# Sonar.net
KiCad netlist of a schematic drawn in Altium Designer
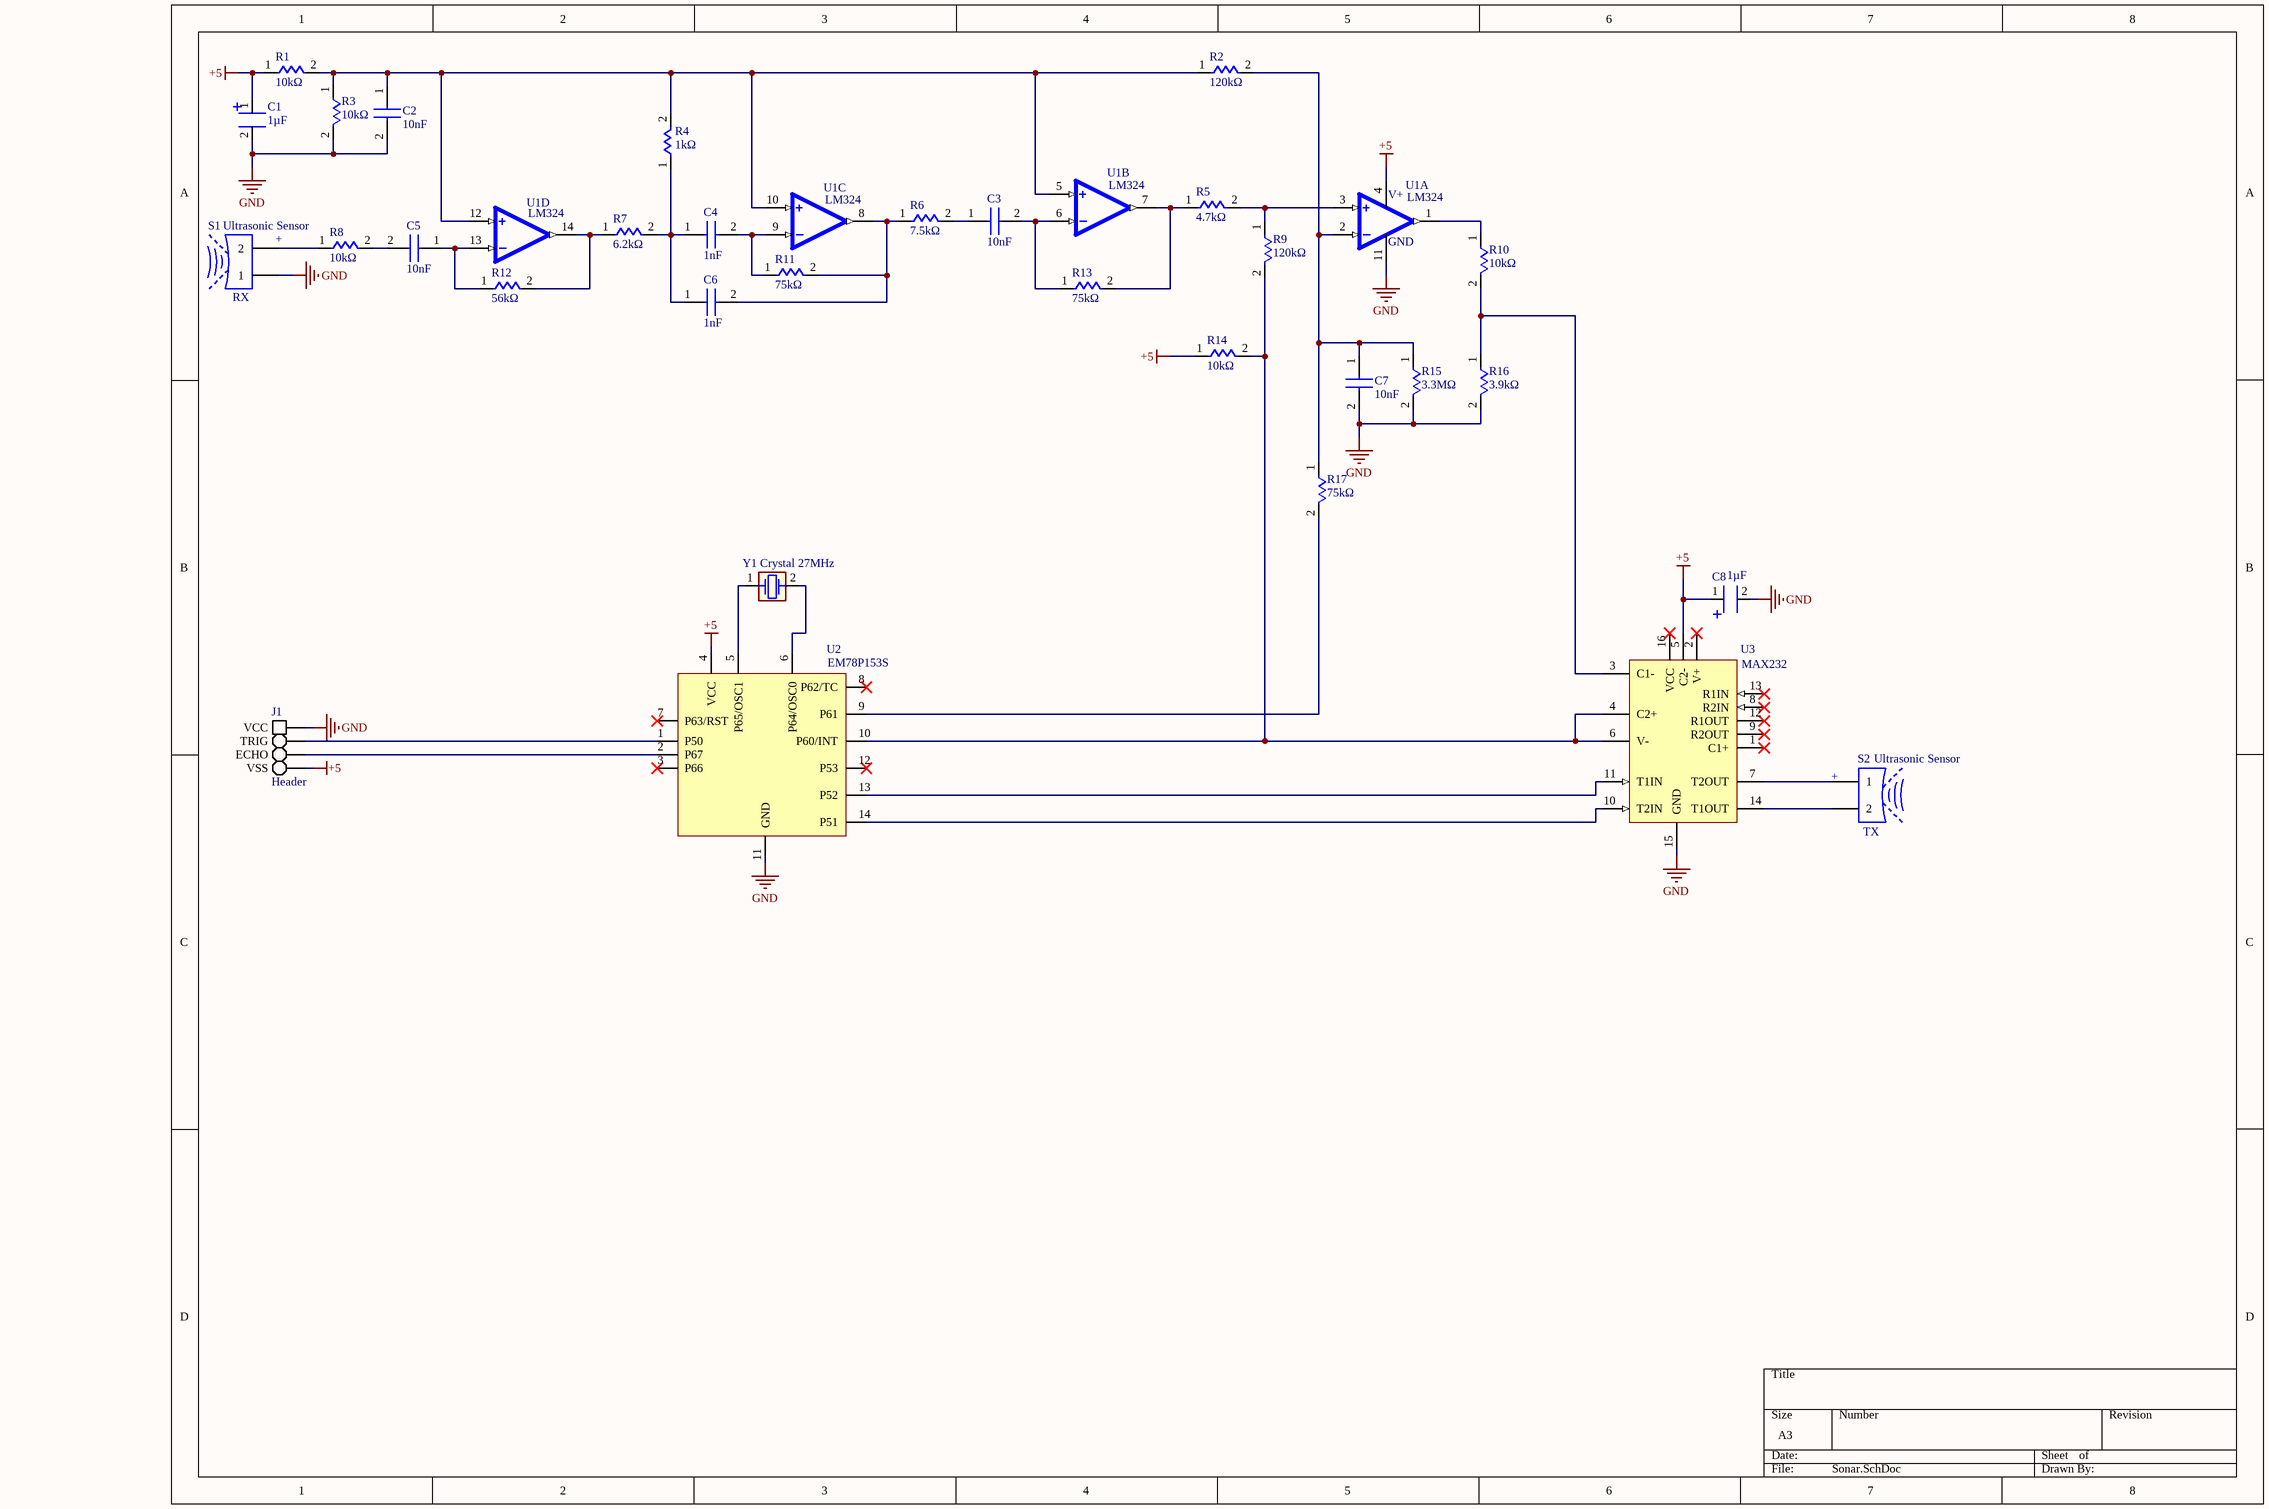
[diagram p0: Sonar.SchDoc]

(export (version "E")
  (design (tool "Eeschema 10.0.6"))
  (components
    (comp (ref "C1")
      (value "1µF")
      (footprint "CAP.EL.")
      (description "MZ1V687M12020PH - CAP.EL.680uF 35V 12.5x20 5MM 105C TB SAMWHA")
      (libsource (lib "Sonar") (part "Cap Pol"))
    )
    (comp (ref "C2")
      (value "10nF")
      (footprint "CAP")
      (description "Capacitor")
      (libsource (lib "Sonar") (part "CAP"))
    )
    (comp (ref "C3")
      (value "10nF")
      (footprint "CAP")
      (description "Capacitor")
      (libsource (lib "Sonar") (part "CAP"))
    )
    (comp (ref "C4")
      (value "1nF")
      (footprint "CAP")
      (description "Capacitor")
      (libsource (lib "Sonar") (part "CAP"))
    )
    (comp (ref "C5")
      (value "10nF")
      (footprint "CAP")
      (description "Capacitor")
      (libsource (lib "Sonar") (part "CAP"))
    )
    (comp (ref "C6")
      (value "1nF")
      (footprint "CAP")
      (description "Capacitor")
      (libsource (lib "Sonar") (part "CAP"))
    )
    (comp (ref "C7")
      (value "10nF")
      (footprint "CAP")
      (description "Capacitor")
      (libsource (lib "Sonar") (part "CAP"))
    )
    (comp (ref "C8")
      (value "1µF")
      (footprint "CAP.EL.")
      (description "MZ1V687M12020PH - CAP.EL.680uF 35V 12.5x20 5MM 105C TB SAMWHA")
      (libsource (lib "Sonar") (part "Cap Pol"))
    )
    (comp (ref "J1") (value "Header") (footprint "Header 1x4") (libsource (lib "Sonar") (part "Header")))
    (comp (ref "R1")
      (value "10kΩ")
      (footprint "THT Res")
      (description "THT RES")
      (libsource (lib "Sonar") (part "THT RES"))
    )
    (comp (ref "R2")
      (value "120kΩ")
      (footprint "THT Res")
      (description "THT RES")
      (libsource (lib "Sonar") (part "THT RES"))
    )
    (comp (ref "R3")
      (value "10kΩ")
      (footprint "THT Res")
      (description "THT RES")
      (libsource (lib "Sonar") (part "THT RES"))
    )
    (comp (ref "R4")
      (value "1kΩ")
      (footprint "THT Res")
      (description "THT RES")
      (libsource (lib "Sonar") (part "THT RES"))
    )
    (comp (ref "R5")
      (value "4.7kΩ")
      (footprint "THT Res")
      (description "THT RES")
      (libsource (lib "Sonar") (part "THT RES"))
    )
    (comp (ref "R6")
      (value "7.5kΩ")
      (footprint "THT Res")
      (description "THT RES")
      (libsource (lib "Sonar") (part "THT RES"))
    )
    (comp (ref "R7")
      (value "6.2kΩ")
      (footprint "THT Res")
      (description "THT RES")
      (libsource (lib "Sonar") (part "THT RES"))
    )
    (comp (ref "R8")
      (value "10kΩ")
      (footprint "THT Res")
      (description "THT RES")
      (libsource (lib "Sonar") (part "THT RES"))
    )
    (comp (ref "R9")
      (value "120kΩ")
      (footprint "THT Res")
      (description "THT RES")
      (libsource (lib "Sonar") (part "THT RES"))
    )
    (comp (ref "R10")
      (value "10kΩ")
      (footprint "THT Res")
      (description "THT RES")
      (libsource (lib "Sonar") (part "THT RES"))
    )
    (comp (ref "R11")
      (value "75kΩ")
      (footprint "THT Res")
      (description "THT RES")
      (libsource (lib "Sonar") (part "THT RES"))
    )
    (comp (ref "R12")
      (value "56kΩ")
      (footprint "THT Res")
      (description "THT RES")
      (libsource (lib "Sonar") (part "THT RES"))
    )
    (comp (ref "R13")
      (value "75kΩ")
      (footprint "THT Res")
      (description "THT RES")
      (libsource (lib "Sonar") (part "THT RES"))
    )
    (comp (ref "R14")
      (value "10kΩ")
      (footprint "THT Res")
      (description "THT RES")
      (libsource (lib "Sonar") (part "THT RES"))
    )
    (comp (ref "R15")
      (value "3.3MΩ")
      (footprint "THT Res")
      (description "THT RES")
      (libsource (lib "Sonar") (part "THT RES"))
    )
    (comp (ref "R16")
      (value "3.9kΩ")
      (footprint "THT Res")
      (description "THT RES")
      (libsource (lib "Sonar") (part "THT RES"))
    )
    (comp (ref "R17")
      (value "75kΩ")
      (footprint "THT Res")
      (description "THT RES")
      (libsource (lib "Sonar") (part "THT RES"))
    )
    (comp (ref "S1")
      (value "Ultrasonic Sensor")
      (footprint "Ultrasonic Sensor")
      (libsource (lib "Sonar") (part "Ultrasonic Sensor"))
    )
    (comp (ref "S2")
      (value "Ultrasonic Sensor")
      (footprint "Ultrasonic Sensor")
      (libsource (lib "Sonar") (part "Ultrasonic Sensor"))
    )
    (comp (ref "U1")
      (value "LM324")
      (footprint "LM324")
      (description "4-Channel industry standard operational amplifier 14-PDIP 0 to 70")
      (fields (field (name "MP") "LM324N") (field (name "MF") "Texas Instruments"))
      (libsource (lib "Sonar") (part "LM324N/NOPB"))
    )
    (comp (ref "U2") (value "EM78P153S") (footprint "EM78P153S") (libsource (lib "Sonar") (part "EM78P153S")))
    (comp (ref "U3")
      (value "MAX232")
      (footprint "MAX232")
      (description "Multichannel RS-232 Driver/Receiver, 5 V, 0 to 70 degC, 16-Pin SOIC (S16+3), RoHS, Tube")
      (fields (field (name "MANUFACTURER") "Maxim"))
      (libsource (lib "Sonar") (part "MAX232"))
    )
    (comp (ref "Y1")
      (value "Crystal 27MHz")
      (footprint "Crsytal")
      (description "27.000 MHz Kristal HC-49S")
      (libsource (lib "Sonar") (part "Crystal"))
    )
  )
  (nets
    (net (code "1") (name "+5") (class "Default")
      (node (ref "C1") (pin "1") (pinfunction "1_1") (pintype "passive"))
      (node (ref "C8") (pin "1") (pinfunction "1_1") (pintype "passive"))
      (node (ref "J1") (pin "4") (pinfunction "VSS_4") (pintype "passive"))
      (node (ref "R1") (pin "1") (pinfunction "1_1") (pintype "passive"))
      (node (ref "R14") (pin "1") (pinfunction "1_1") (pintype "passive"))
      (node (ref "U1") (pin "4") (pinfunction "V+_4") (pintype "power_in"))
      (node (ref "U2") (pin "4") (pinfunction "VCC_4") (pintype "passive"))
      (node (ref "U3") (pin "5") (pinfunction "C2-_5") (pintype "passive"))
    )
    (net (code "2") (name "GND") (class "Default")
      (node (ref "C1") (pin "2") (pinfunction "2_2") (pintype "passive"))
      (node (ref "C2") (pin "2") (pinfunction "2_2") (pintype "passive"))
      (node (ref "C7") (pin "2") (pinfunction "2_2") (pintype "passive"))
      (node (ref "C8") (pin "2") (pinfunction "2_2") (pintype "passive"))
      (node (ref "J1") (pin "1") (pinfunction "VCC_1") (pintype "passive"))
      (node (ref "R15") (pin "2") (pinfunction "2_2") (pintype "passive"))
      (node (ref "R16") (pin "2") (pinfunction "2_2") (pintype "passive"))
      (node (ref "R3") (pin "2") (pinfunction "2_2") (pintype "passive"))
      (node (ref "S1") (pin "1") (pinfunction "1_1") (pintype "passive"))
      (node (ref "U1") (pin "11") (pinfunction "GND_11") (pintype "power_in"))
      (node (ref "U2") (pin "11") (pinfunction "GND_11") (pintype "passive"))
      (node (ref "U3") (pin "15") (pinfunction "GND_15") (pintype "power_in"))
    )
    (net (code "3") (name "Net-(C3-Pad1)") (class "Default")
      (node (ref "C3") (pin "1") (pinfunction "1_1") (pintype "passive"))
      (node (ref "R6") (pin "2") (pinfunction "2_2") (pintype "passive"))
    )
    (net (code "4") (name "Net-(C4-Pad1)") (class "Default")
      (node (ref "C4") (pin "1") (pinfunction "1_1") (pintype "passive"))
      (node (ref "C6") (pin "1") (pinfunction "1_1") (pintype "passive"))
      (node (ref "R4") (pin "1") (pinfunction "1_1") (pintype "passive"))
      (node (ref "R7") (pin "2") (pinfunction "2_2") (pintype "passive"))
    )
    (net (code "5") (name "Net-(C5-Pad2)") (class "Default")
      (node (ref "C5") (pin "2") (pinfunction "2_2") (pintype "passive"))
      (node (ref "R8") (pin "2") (pinfunction "2_2") (pintype "passive"))
    )
    (net (code "6") (name "Net-(J1-ECHO)") (class "Default")
      (node (ref "J1") (pin "3") (pinfunction "ECHO_3") (pintype "passive"))
      (node (ref "U2") (pin "2") (pinfunction "P67_2") (pintype "passive"))
    )
    (net (code "7") (name "Net-(J1-TRIG)") (class "Default")
      (node (ref "J1") (pin "2") (pinfunction "TRIG_2") (pintype "passive"))
      (node (ref "U2") (pin "1") (pinfunction "P50_1") (pintype "passive"))
    )
    (net (code "8") (name "Net-(R8-Pad1)") (class "Default")
      (node (ref "R8") (pin "1") (pinfunction "1_1") (pintype "passive"))
      (node (ref "S1") (pin "2") (pinfunction "2_2") (pintype "passive"))
    )
    (net (code "9") (name "Net-(U1A-1IN+)") (class "Default")
      (node (ref "R5") (pin "2") (pinfunction "2_2") (pintype "passive"))
      (node (ref "R9") (pin "1") (pinfunction "1_1") (pintype "passive"))
      (node (ref "U1") (pin "3") (pinfunction "1IN+_3") (pintype "input"))
    )
    (net (code "10") (name "Net-(U1A-1IN-)") (class "Default")
      (node (ref "C7") (pin "1") (pinfunction "1_1") (pintype "passive"))
      (node (ref "R15") (pin "1") (pinfunction "1_1") (pintype "passive"))
      (node (ref "R17") (pin "1") (pinfunction "1_1") (pintype "passive"))
      (node (ref "R2") (pin "2") (pinfunction "2_2") (pintype "passive"))
      (node (ref "U1") (pin "2") (pinfunction "1IN-_2") (pintype "input"))
    )
    (net (code "11") (name "Net-(U1A-1OUT)") (class "Default")
      (node (ref "R10") (pin "1") (pinfunction "1_1") (pintype "passive"))
      (node (ref "U1") (pin "1") (pinfunction "1OUT_1") (pintype "output"))
    )
    (net (code "12") (name "Net-(U1B-2IN+)") (class "Default")
      (node (ref "C2") (pin "1") (pinfunction "1_1") (pintype "passive"))
      (node (ref "R1") (pin "2") (pinfunction "2_2") (pintype "passive"))
      (node (ref "R2") (pin "1") (pinfunction "1_1") (pintype "passive"))
      (node (ref "R3") (pin "1") (pinfunction "1_1") (pintype "passive"))
      (node (ref "R4") (pin "2") (pinfunction "2_2") (pintype "passive"))
      (node (ref "U1") (pin "10") (pinfunction "3IN+_10") (pintype "input"))
      (node (ref "U1") (pin "12") (pinfunction "4IN+_12") (pintype "input"))
      (node (ref "U1") (pin "5") (pinfunction "2IN+_5") (pintype "input"))
    )
    (net (code "13") (name "Net-(U1B-2IN-)") (class "Default")
      (node (ref "C3") (pin "2") (pinfunction "2_2") (pintype "passive"))
      (node (ref "R13") (pin "1") (pinfunction "1_1") (pintype "passive"))
      (node (ref "U1") (pin "6") (pinfunction "2IN-_6") (pintype "input"))
    )
    (net (code "14") (name "Net-(U1B-2OUT)") (class "Default")
      (node (ref "R13") (pin "2") (pinfunction "2_2") (pintype "passive"))
      (node (ref "R5") (pin "1") (pinfunction "1_1") (pintype "passive"))
      (node (ref "U1") (pin "7") (pinfunction "2OUT_7") (pintype "output"))
    )
    (net (code "15") (name "Net-(U1C-3IN-)") (class "Default")
      (node (ref "C4") (pin "2") (pinfunction "2_2") (pintype "passive"))
      (node (ref "R11") (pin "1") (pinfunction "1_1") (pintype "passive"))
      (node (ref "U1") (pin "9") (pinfunction "3IN-_9") (pintype "input"))
    )
    (net (code "16") (name "Net-(U1C-3OUT)") (class "Default")
      (node (ref "C6") (pin "2") (pinfunction "2_2") (pintype "passive"))
      (node (ref "R11") (pin "2") (pinfunction "2_2") (pintype "passive"))
      (node (ref "R6") (pin "1") (pinfunction "1_1") (pintype "passive"))
      (node (ref "U1") (pin "8") (pinfunction "3OUT_8") (pintype "output"))
    )
    (net (code "17") (name "Net-(U1D-4IN-)") (class "Default")
      (node (ref "C5") (pin "1") (pinfunction "1_1") (pintype "passive"))
      (node (ref "R12") (pin "1") (pinfunction "1_1") (pintype "passive"))
      (node (ref "U1") (pin "13") (pinfunction "4IN-_13") (pintype "input"))
    )
    (net (code "18") (name "Net-(U1D-4OUT)") (class "Default")
      (node (ref "R12") (pin "2") (pinfunction "2_2") (pintype "passive"))
      (node (ref "R7") (pin "1") (pinfunction "1_1") (pintype "passive"))
      (node (ref "U1") (pin "14") (pinfunction "4OUT_14") (pintype "output"))
    )
    (net (code "19") (name "Net-(U2-P51)") (class "Default")
      (node (ref "U2") (pin "14") (pinfunction "P51_14") (pintype "passive"))
      (node (ref "U3") (pin "10") (pinfunction "T2IN_10") (pintype "input"))
    )
    (net (code "20") (name "Net-(U2-P52)") (class "Default")
      (node (ref "U2") (pin "13") (pinfunction "P52_13") (pintype "passive"))
      (node (ref "U3") (pin "11") (pinfunction "T1IN_11") (pintype "input"))
    )
    (net (code "21") (name "Net-(U2-P60{slash}INT)") (class "Default")
      (node (ref "R14") (pin "2") (pinfunction "2_2") (pintype "passive"))
      (node (ref "R9") (pin "2") (pinfunction "2_2") (pintype "passive"))
      (node (ref "U2") (pin "10") (pinfunction "P60/INT_10") (pintype "passive"))
      (node (ref "U3") (pin "4") (pinfunction "C2+_4") (pintype "passive"))
      (node (ref "U3") (pin "6") (pinfunction "V-_6") (pintype "power_in"))
    )
    (net (code "22") (name "Net-(U2-P61)") (class "Default")
      (node (ref "R17") (pin "2") (pinfunction "2_2") (pintype "passive"))
      (node (ref "U2") (pin "9") (pinfunction "P61_9") (pintype "passive"))
    )
    (net (code "23") (name "Net-(U2-P64{slash}OSC0)") (class "Default")
      (node (ref "U2") (pin "6") (pinfunction "P64/OSC0_6") (pintype "passive"))
      (node (ref "Y1") (pin "2") (pinfunction "2_2") (pintype "power_in"))
    )
    (net (code "24") (name "Net-(U2-P65{slash}OSC1)") (class "Default")
      (node (ref "U2") (pin "5") (pinfunction "P65/OSC1_5") (pintype "passive"))
      (node (ref "Y1") (pin "1") (pinfunction "1_1") (pintype "power_in"))
    )
    (net (code "25") (name "Net-(U3-C1-)") (class "Default")
      (node (ref "R10") (pin "2") (pinfunction "2_2") (pintype "passive"))
      (node (ref "R16") (pin "1") (pinfunction "1_1") (pintype "passive"))
      (node (ref "U3") (pin "3") (pinfunction "C1-_3") (pintype "passive"))
    )
    (net (code "26") (name "Net-(U3-T1OUT)") (class "Default")
      (node (ref "S2") (pin "2") (pinfunction "2_2") (pintype "passive"))
      (node (ref "U3") (pin "14") (pinfunction "T1OUT_14") (pintype "tri_state"))
    )
    (net (code "27") (name "Net-(U3-T2OUT)") (class "Default")
      (node (ref "S2") (pin "1") (pinfunction "1_1") (pintype "passive"))
      (node (ref "U3") (pin "7") (pinfunction "T2OUT_7") (pintype "tri_state"))
    )
    (net (code "28") (name "unconnected-(U2-P53-Pad12)") (class "Default")
      (node (ref "U2") (pin "12") (pinfunction "P53_12") (pintype "passive+no_connect"))
    )
    (net (code "29") (name "unconnected-(U2-P62{slash}TC-Pad8)") (class "Default")
      (node (ref "U2") (pin "8") (pinfunction "P62/TC_8") (pintype "passive+no_connect"))
    )
    (net (code "30") (name "unconnected-(U2-P63{slash}RST-Pad7)") (class "Default")
      (node (ref "U2") (pin "7") (pinfunction "P63/RST_7") (pintype "passive+no_connect"))
    )
    (net (code "31") (name "unconnected-(U2-P66-Pad3)") (class "Default")
      (node (ref "U2") (pin "3") (pinfunction "P66_3") (pintype "passive+no_connect"))
    )
    (net (code "32") (name "unconnected-(U3-C1+-Pad1)") (class "Default")
      (node (ref "U3") (pin "1") (pinfunction "C1+_1") (pintype "passive+no_connect"))
    )
    (net (code "33") (name "unconnected-(U3-R1IN-Pad13)") (class "Default")
      (node (ref "U3") (pin "13") (pinfunction "R1IN_13") (pintype "input+no_connect"))
    )
    (net (code "34") (name "unconnected-(U3-R1OUT-Pad12)") (class "Default")
      (node (ref "U3") (pin "12") (pinfunction "R1OUT_12") (pintype "tri_state+no_connect"))
    )
    (net (code "35") (name "unconnected-(U3-R2IN-Pad8)") (class "Default")
      (node (ref "U3") (pin "8") (pinfunction "R2IN_8") (pintype "input+no_connect"))
    )
    (net (code "36") (name "unconnected-(U3-R2OUT-Pad9)") (class "Default")
      (node (ref "U3") (pin "9") (pinfunction "R2OUT_9") (pintype "tri_state+no_connect"))
    )
    (net (code "37") (name "unconnected-(U3-V+-Pad2)") (class "Default")
      (node (ref "U3") (pin "2") (pinfunction "V+_2") (pintype "power_in+no_connect"))
    )
    (net (code "38") (name "unconnected-(U3-VCC-Pad16)") (class "Default")
      (node (ref "U3") (pin "16") (pinfunction "VCC_16") (pintype "power_in+no_connect"))
    )
  )
)
